# 4led-indicator.net
KiCad netlist of a schematic drawn in EAGLE
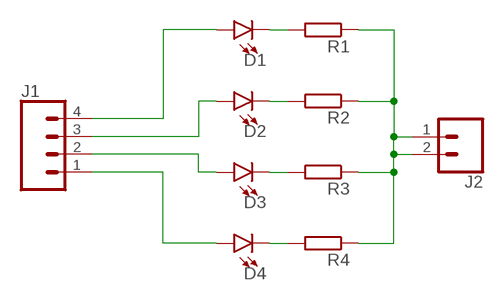
[diagram p0: schematic, sheet 1]

(export (version "E")
  (design (tool "Eeschema 10.0.6"))
  (components
    (comp (ref "D1")
      (value "LED0603")
      (footprint "eagle-import:LED-0603")
      (libsource (lib "eagle-import") (part "LED0603"))
    )
    (comp (ref "D2")
      (value "LED0603")
      (footprint "eagle-import:LED-0603")
      (libsource (lib "eagle-import") (part "LED0603"))
    )
    (comp (ref "D3")
      (value "LED0603")
      (footprint "eagle-import:LED-0603")
      (libsource (lib "eagle-import") (part "LED0603"))
    )
    (comp (ref "D4")
      (value "LED0603")
      (footprint "eagle-import:LED-0603")
      (libsource (lib "eagle-import") (part "LED0603"))
    )
    (comp (ref "J1")
      (value "CONN_04LOCK")
      (footprint "eagle-import:1X04_LOCK")
      (libsource (lib "eagle-import") (part "CONN_04LOCK"))
    )
    (comp (ref "J2")
      (value "CONN_02LOCK")
      (footprint "eagle-import:1X02_LOCK")
      (libsource (lib "eagle-import") (part "CONN_02LOCK"))
    )
    (comp (ref "R1")
      (value "RESISTOR-EU_R0603")
      (footprint "eagle-import:R0603")
      (libsource (lib "eagle-import") (part "RESISTOR-EU_R0603"))
    )
    (comp (ref "R2")
      (value "RESISTOR-EU_R0603")
      (footprint "eagle-import:R0603")
      (libsource (lib "eagle-import") (part "RESISTOR-EU_R0603"))
    )
    (comp (ref "R3")
      (value "RESISTOR-EU_R0603")
      (footprint "eagle-import:R0603")
      (libsource (lib "eagle-import") (part "RESISTOR-EU_R0603"))
    )
    (comp (ref "R4")
      (value "RESISTOR-EU_R0603")
      (footprint "eagle-import:R0603")
      (libsource (lib "eagle-import") (part "RESISTOR-EU_R0603"))
    )
  )
  (nets
    (net (code "1") (name "Net-(D1-PadA)") (class "Default")
      (node (ref "D1") (pin "A") (pinfunction "A_A") (pintype "passive"))
      (node (ref "J1") (pin "4") (pinfunction "4_4") (pintype "passive"))
    )
    (net (code "2") (name "Net-(D1-PadC)") (class "Default")
      (node (ref "D1") (pin "C") (pinfunction "C_C") (pintype "passive"))
      (node (ref "R1") (pin "2") (pinfunction "2_2") (pintype "passive"))
    )
    (net (code "3") (name "Net-(D2-PadA)") (class "Default")
      (node (ref "D2") (pin "A") (pinfunction "A_A") (pintype "passive"))
      (node (ref "J1") (pin "3") (pinfunction "3_3") (pintype "passive"))
    )
    (net (code "4") (name "Net-(D2-PadC)") (class "Default")
      (node (ref "D2") (pin "C") (pinfunction "C_C") (pintype "passive"))
      (node (ref "R2") (pin "2") (pinfunction "2_2") (pintype "passive"))
    )
    (net (code "5") (name "Net-(D3-PadA)") (class "Default")
      (node (ref "D3") (pin "A") (pinfunction "A_A") (pintype "passive"))
      (node (ref "J1") (pin "2") (pinfunction "2_2") (pintype "passive"))
    )
    (net (code "6") (name "Net-(D3-PadC)") (class "Default")
      (node (ref "D3") (pin "C") (pinfunction "C_C") (pintype "passive"))
      (node (ref "R3") (pin "2") (pinfunction "2_2") (pintype "passive"))
    )
    (net (code "7") (name "Net-(D4-PadA)") (class "Default")
      (node (ref "D4") (pin "A") (pinfunction "A_A") (pintype "passive"))
      (node (ref "J1") (pin "1") (pinfunction "1_1") (pintype "passive"))
    )
    (net (code "8") (name "Net-(D4-PadC)") (class "Default")
      (node (ref "D4") (pin "C") (pinfunction "C_C") (pintype "passive"))
      (node (ref "R4") (pin "2") (pinfunction "2_2") (pintype "passive"))
    )
    (net (code "9") (name "Net-(J2-Pad1)") (class "Default")
      (node (ref "J2") (pin "1") (pinfunction "1_1") (pintype "passive"))
      (node (ref "J2") (pin "2") (pinfunction "2_2") (pintype "passive"))
      (node (ref "R1") (pin "1") (pinfunction "1_1") (pintype "passive"))
      (node (ref "R2") (pin "1") (pinfunction "1_1") (pintype "passive"))
      (node (ref "R3") (pin "1") (pinfunction "1_1") (pintype "passive"))
      (node (ref "R4") (pin "1") (pinfunction "1_1") (pintype "passive"))
    )
  )
)
